# Line_follwer.net
KiCad netlist of a schematic drawn in EAGLE
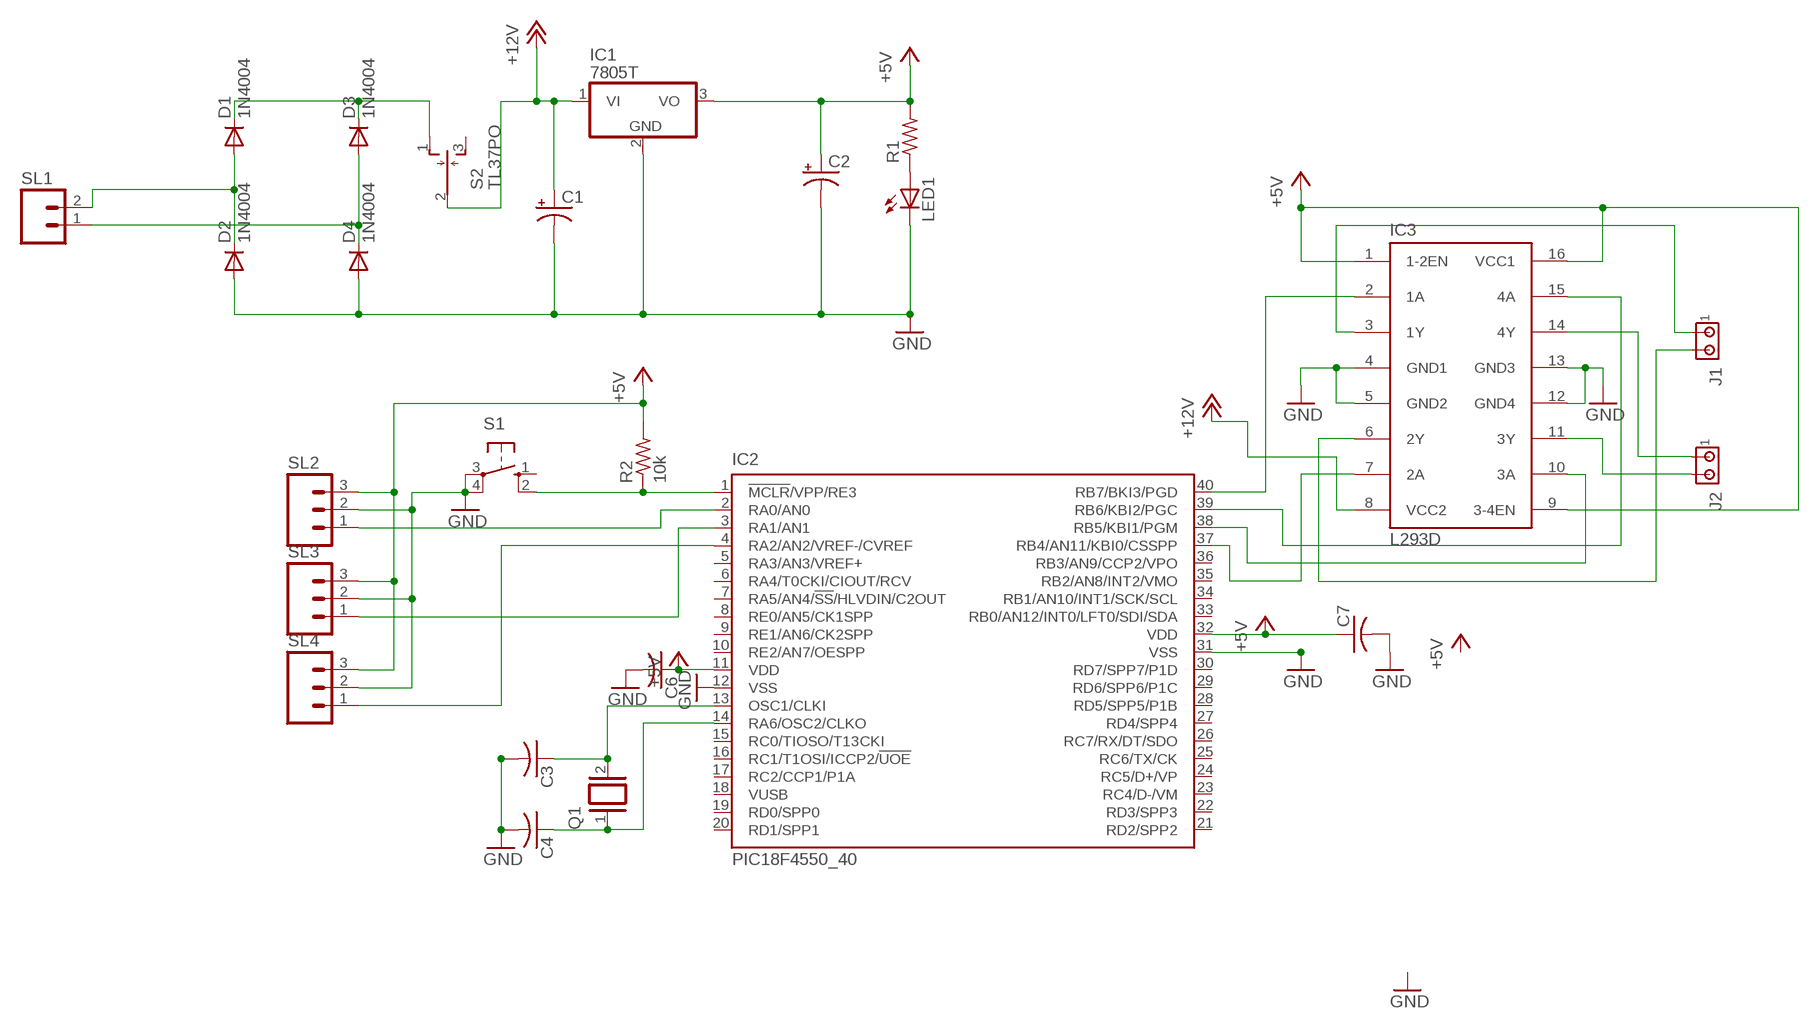
[diagram p0: schematic, sheet 1]

(export (version "E")
  (design (tool "Eeschema 10.0.6"))
  (components
    (comp (ref "C1")
      (value "CPOL-USE3.5-8")
      (footprint "eagle-import:E3,5-8")
      (libsource (lib "eagle-import") (part "CPOL-USE3.5-8"))
    )
    (comp (ref "C2")
      (value "CPOL-USE3.5-8")
      (footprint "eagle-import:E3,5-8")
      (libsource (lib "eagle-import") (part "CPOL-USE3.5-8"))
    )
    (comp (ref "C3")
      (value "C-US025-024X044")
      (footprint "eagle-import:C025-024X044")
      (libsource (lib "eagle-import") (part "C-US025-024X044"))
    )
    (comp (ref "C4")
      (value "C-US025-024X044")
      (footprint "eagle-import:C025-024X044")
      (libsource (lib "eagle-import") (part "C-US025-024X044"))
    )
    (comp (ref "C6")
      (value "C-US025-024X044")
      (footprint "eagle-import:C025-024X044")
      (libsource (lib "eagle-import") (part "C-US025-024X044"))
    )
    (comp (ref "C7")
      (value "C-US025-024X044")
      (footprint "eagle-import:C025-024X044")
      (libsource (lib "eagle-import") (part "C-US025-024X044"))
    )
    (comp (ref "D1")
      (value "1N4004")
      (footprint "eagle-import:DO41-10")
      (libsource (lib "eagle-import") (part "1N4004"))
    )
    (comp (ref "D2")
      (value "1N4004")
      (footprint "eagle-import:DO41-10")
      (libsource (lib "eagle-import") (part "1N4004"))
    )
    (comp (ref "D3")
      (value "1N4004")
      (footprint "eagle-import:DO41-10")
      (libsource (lib "eagle-import") (part "1N4004"))
    )
    (comp (ref "D4")
      (value "1N4004")
      (footprint "eagle-import:DO41-10")
      (libsource (lib "eagle-import") (part "1N4004"))
    )
    (comp (ref "IC1")
      (value "7805T")
      (footprint "eagle-import:TO220H")
      (libsource (lib "eagle-import") (part "78T05"))
    )
    (comp (ref "IC2")
      (value "PIC18F4550_40")
      (footprint "eagle-import:DIL40")
      (fields (field (name "MF") "MICROCHIP") (field (name "MPN") "PIC18F4550-I/P"))
      (libsource (lib "eagle-import") (part "PIC18F4_40550"))
    )
    (comp (ref "IC3")
      (value "L293D")
      (footprint "eagle-import:DIL16")
      (libsource (lib "eagle-import") (part "L293D"))
    )
    (comp (ref "J1")
      (value "MTA02-100")
      (footprint "eagle-import:10X02MTA")
      (libsource (lib "eagle-import") (part "MTA02-100"))
    )
    (comp (ref "J2")
      (value "MTA02-100")
      (footprint "eagle-import:10X02MTA")
      (libsource (lib "eagle-import") (part "MTA02-100"))
    )
    (comp (ref "LED1")
      (value "LED5MM")
      (footprint "eagle-import:LED5MM")
      (libsource (lib "eagle-import") (part "LED5MM"))
    )
    (comp (ref "Q1")
      (value "XTAL/S")
      (footprint "eagle-import:QS")
      (libsource (lib "eagle-import") (part "XTAL/S"))
    )
    (comp (ref "R1")
      (value "R-US_0207/10")
      (footprint "eagle-import:0207_10")
      (libsource (lib "eagle-import") (part "R-US_0207/10"))
    )
    (comp (ref "R2")
      (value "10k")
      (footprint "eagle-import:0207_10")
      (libsource (lib "eagle-import") (part "R-US_0207/10"))
    )
    (comp (ref "S1")
      (value "10-XX")
      (footprint "eagle-import:B3F-10XX")
      (fields (field (name "MPN") "B3F-1000"))
      (libsource (lib "eagle-import") (part "10-XX"))
    )
    (comp (ref "S2")
      (value "TL37PO")
      (footprint "eagle-import:TL3XPO")
      (libsource (lib "eagle-import") (part "TL37PO"))
    )
    (comp (ref "SL1")
      (value "MA02")
      (footprint "eagle-import:02PA")
      (libsource (lib "eagle-import") (part "MA02"))
    )
    (comp (ref "SL2")
      (value "MA03")
      (footprint "eagle-import:03P")
      (libsource (lib "eagle-import") (part "MA03"))
    )
    (comp (ref "SL3")
      (value "MA03")
      (footprint "eagle-import:03P")
      (libsource (lib "eagle-import") (part "MA03"))
    )
    (comp (ref "SL4")
      (value "MA03")
      (footprint "eagle-import:03P")
      (libsource (lib "eagle-import") (part "MA03"))
    )
  )
  (nets
    (net (code "1") (name "+5V") (class "Default")
      (node (ref "C2") (pin "+") (pinfunction "+_+") (pintype "passive"))
      (node (ref "C6") (pin "1") (pinfunction "1_1") (pintype "passive"))
      (node (ref "C7") (pin "1") (pinfunction "1_1") (pintype "passive"))
      (node (ref "IC1") (pin "3") (pinfunction "VO_3") (pintype "passive"))
      (node (ref "IC2") (pin "11") (pinfunction "VDD_11") (pintype "power_in"))
      (node (ref "IC2") (pin "32") (pinfunction "VDD_32") (pintype "power_in"))
      (node (ref "IC3") (pin "1") (pinfunction "1-2EN_1") (pintype "input"))
      (node (ref "IC3") (pin "16") (pinfunction "VCC1_16") (pintype "power_in"))
      (node (ref "IC3") (pin "9") (pinfunction "3-4EN_9") (pintype "input"))
      (node (ref "R1") (pin "2") (pinfunction "2_2") (pintype "passive"))
      (node (ref "R2") (pin "2") (pinfunction "2_2") (pintype "passive"))
      (node (ref "SL2") (pin "3") (pinfunction "3_3") (pintype "passive"))
      (node (ref "SL3") (pin "3") (pinfunction "3_3") (pintype "passive"))
      (node (ref "SL4") (pin "3") (pinfunction "3_3") (pintype "passive"))
    )
    (net (code "2") (name "+12V") (class "Default")
      (node (ref "C1") (pin "+") (pinfunction "+_+") (pintype "passive"))
      (node (ref "IC1") (pin "1") (pinfunction "VI_1") (pintype "input"))
      (node (ref "IC3") (pin "8") (pinfunction "VCC2_8") (pintype "power_in"))
      (node (ref "S2") (pin "2") (pinfunction "P_2") (pintype "passive"))
    )
    (net (code "3") (name "GND") (class "Default")
      (node (ref "C1") (pin "-") (pinfunction "-_-") (pintype "passive"))
      (node (ref "C2") (pin "-") (pinfunction "-_-") (pintype "passive"))
      (node (ref "C3") (pin "2") (pinfunction "2_2") (pintype "passive"))
      (node (ref "C4") (pin "2") (pinfunction "2_2") (pintype "passive"))
      (node (ref "C6") (pin "2") (pinfunction "2_2") (pintype "passive"))
      (node (ref "C7") (pin "2") (pinfunction "2_2") (pintype "passive"))
      (node (ref "D2") (pin "A") (pinfunction "A_A") (pintype "passive"))
      (node (ref "D4") (pin "A") (pinfunction "A_A") (pintype "passive"))
      (node (ref "IC1") (pin "2") (pinfunction "GND_2") (pintype "passive"))
      (node (ref "IC2") (pin "12") (pinfunction "VSS_12") (pintype "power_in"))
      (node (ref "IC2") (pin "31") (pinfunction "VSS_31") (pintype "power_in"))
      (node (ref "IC3") (pin "12") (pinfunction "GND4_12") (pintype "power_in"))
      (node (ref "IC3") (pin "13") (pinfunction "GND3_13") (pintype "power_in"))
      (node (ref "IC3") (pin "4") (pinfunction "GND1_4") (pintype "power_in"))
      (node (ref "IC3") (pin "5") (pinfunction "GND2_5") (pintype "power_in"))
      (node (ref "LED1") (pin "K") (pinfunction "C_K") (pintype "passive"))
      (node (ref "S1") (pin "3") (pinfunction "P_3") (pintype "passive"))
      (node (ref "S1") (pin "4") (pinfunction "P1_4") (pintype "passive"))
      (node (ref "SL2") (pin "2") (pinfunction "2_2") (pintype "passive"))
      (node (ref "SL3") (pin "2") (pinfunction "2_2") (pintype "passive"))
      (node (ref "SL4") (pin "2") (pinfunction "2_2") (pintype "passive"))
    )
    (net (code "4") (name "Net-(D1-PadA)") (class "Default")
      (node (ref "D1") (pin "A") (pinfunction "A_A") (pintype "passive"))
      (node (ref "D2") (pin "C") (pinfunction "C_C") (pintype "passive"))
      (node (ref "SL1") (pin "2") (pinfunction "2_2") (pintype "passive"))
    )
    (net (code "5") (name "Net-(D3-PadA)") (class "Default")
      (node (ref "D3") (pin "A") (pinfunction "A_A") (pintype "passive"))
      (node (ref "D4") (pin "C") (pinfunction "C_C") (pintype "passive"))
      (node (ref "SL1") (pin "1") (pinfunction "1_1") (pintype "passive"))
    )
    (net (code "6") (name "Net-(IC2-OSC1{slash}CLKI)") (class "Default")
      (node (ref "C3") (pin "1") (pinfunction "1_1") (pintype "passive"))
      (node (ref "IC2") (pin "13") (pinfunction "OSC1/CLKI_13") (pintype "input"))
      (node (ref "Q1") (pin "2") (pinfunction "2_2") (pintype "passive"))
    )
    (net (code "7") (name "Net-(IC2-RA0{slash}AN0)") (class "Default")
      (node (ref "IC2") (pin "2") (pinfunction "RA0/AN0_2") (pintype "bidirectional"))
      (node (ref "SL2") (pin "1") (pinfunction "1_1") (pintype "passive"))
    )
    (net (code "8") (name "Net-(IC2-RA1{slash}AN1)") (class "Default")
      (node (ref "IC2") (pin "3") (pinfunction "RA1/AN1_3") (pintype "bidirectional"))
      (node (ref "SL3") (pin "1") (pinfunction "1_1") (pintype "passive"))
    )
    (net (code "9") (name "Net-(IC2-RA2{slash}AN2{slash}VREF-{slash}CVREF)") (class "Default")
      (node (ref "IC2") (pin "4") (pinfunction "RA2/AN2/VREF-/CVREF_4") (pintype "bidirectional"))
      (node (ref "SL4") (pin "1") (pinfunction "1_1") (pintype "passive"))
    )
    (net (code "10") (name "Net-(IC2-RA6{slash}OSC2{slash}CLKO)") (class "Default")
      (node (ref "C4") (pin "1") (pinfunction "1_1") (pintype "passive"))
      (node (ref "IC2") (pin "14") (pinfunction "RA6/OSC2/CLKO_14") (pintype "output"))
      (node (ref "Q1") (pin "1") (pinfunction "1_1") (pintype "passive"))
    )
    (net (code "11") (name "Net-(IC2-RB4{slash}AN11{slash}KBI0{slash}CSSPP)") (class "Default")
      (node (ref "IC2") (pin "37") (pinfunction "RB4/AN11/KBI0/CSSPP_37") (pintype "bidirectional"))
      (node (ref "IC3") (pin "7") (pinfunction "2A_7") (pintype "input"))
    )
    (net (code "12") (name "Net-(IC2-RB5{slash}KBI1{slash}PGM)") (class "Default")
      (node (ref "IC2") (pin "38") (pinfunction "RB5/KBI1/PGM_38") (pintype "bidirectional"))
      (node (ref "IC3") (pin "10") (pinfunction "3A_10") (pintype "input"))
    )
    (net (code "13") (name "Net-(IC2-RB6{slash}KBI2{slash}PGC)") (class "Default")
      (node (ref "IC2") (pin "39") (pinfunction "RB6/KBI2/PGC_39") (pintype "bidirectional"))
      (node (ref "IC3") (pin "15") (pinfunction "4A_15") (pintype "input"))
    )
    (net (code "14") (name "Net-(IC2-RB7{slash}BKI3{slash}PGD)") (class "Default")
      (node (ref "IC2") (pin "40") (pinfunction "RB7/BKI3/PGD_40") (pintype "bidirectional"))
      (node (ref "IC3") (pin "2") (pinfunction "1A_2") (pintype "input"))
    )
    (net (code "15") (name "Net-(IC2-~{MCLR}{slash}VPP{slash}RE3)") (class "Default")
      (node (ref "IC2") (pin "1") (pinfunction "~{MCLR}/VPP/RE3_1") (pintype "input"))
      (node (ref "R2") (pin "1") (pinfunction "1_1") (pintype "passive"))
      (node (ref "S1") (pin "2") (pinfunction "S1_2") (pintype "passive"))
    )
    (net (code "16") (name "Net-(IC3-1Y)") (class "Default")
      (node (ref "IC3") (pin "3") (pinfunction "1Y_3") (pintype "output"))
      (node (ref "J1") (pin "1") (pinfunction "1_1") (pintype "passive"))
    )
    (net (code "17") (name "Net-(IC3-2Y)") (class "Default")
      (node (ref "IC3") (pin "6") (pinfunction "2Y_6") (pintype "output"))
      (node (ref "J1") (pin "2") (pinfunction "2_2") (pintype "passive"))
    )
    (net (code "18") (name "Net-(IC3-3Y)") (class "Default")
      (node (ref "IC3") (pin "11") (pinfunction "3Y_11") (pintype "output"))
      (node (ref "J2") (pin "2") (pinfunction "2_2") (pintype "passive"))
    )
    (net (code "19") (name "Net-(IC3-4Y)") (class "Default")
      (node (ref "IC3") (pin "14") (pinfunction "4Y_14") (pintype "output"))
      (node (ref "J2") (pin "1") (pinfunction "1_1") (pintype "passive"))
    )
    (net (code "20") (name "Net-(LED1-PadA)") (class "Default")
      (node (ref "LED1") (pin "A") (pinfunction "A_A") (pintype "passive"))
      (node (ref "R1") (pin "1") (pinfunction "1_1") (pintype "passive"))
    )
    (net (code "21") (name "Net-(S2-O)") (class "Default")
      (node (ref "D1") (pin "C") (pinfunction "C_C") (pintype "passive"))
      (node (ref "D3") (pin "C") (pinfunction "C_C") (pintype "passive"))
      (node (ref "S2") (pin "1") (pinfunction "O_1") (pintype "passive"))
    )
    (net (code "22") (name "unconnected-(IC2-RA3{slash}AN3{slash}VREF+-Pad5)") (class "Default")
      (node (ref "IC2") (pin "5") (pinfunction "RA3/AN3/VREF+_5") (pintype "bidirectional"))
    )
    (net (code "23") (name "unconnected-(IC2-RA4{slash}T0CKI{slash}CIOUT{slash}RCV-Pad6)") (class "Default")
      (node (ref "IC2") (pin "6") (pinfunction "RA4/T0CKI/CIOUT/RCV_6") (pintype "bidirectional"))
    )
    (net (code "24") (name "unconnected-(IC2-RA5{slash}AN4{slash}~{SS}{slash}HLVDIN{slash}C2OUT-Pad7)") (class "Default")
      (node (ref "IC2") (pin "7") (pinfunction "RA5/AN4/~{SS}/HLVDIN/C2OUT_7") (pintype "bidirectional"))
    )
    (net (code "25") (name "unconnected-(IC2-RB0{slash}AN12{slash}INT0{slash}LFT0{slash}SDI{slash}SDA-Pad33)") (class "Default")
      (node (ref "IC2") (pin "33") (pinfunction "RB0/AN12/INT0/LFT0/SDI/SDA_33") (pintype "bidirectional"))
    )
    (net (code "26") (name "unconnected-(IC2-RB1{slash}AN10{slash}INT1{slash}SCK{slash}SCL-Pad34)") (class "Default")
      (node (ref "IC2") (pin "34") (pinfunction "RB1/AN10/INT1/SCK/SCL_34") (pintype "bidirectional"))
    )
    (net (code "27") (name "unconnected-(IC2-RB2{slash}AN8{slash}INT2{slash}VMO-Pad35)") (class "Default")
      (node (ref "IC2") (pin "35") (pinfunction "RB2/AN8/INT2/VMO_35") (pintype "bidirectional"))
    )
    (net (code "28") (name "unconnected-(IC2-RB3{slash}AN9{slash}CCP2{slash}VPO-Pad36)") (class "Default")
      (node (ref "IC2") (pin "36") (pinfunction "RB3/AN9/CCP2/VPO_36") (pintype "bidirectional"))
    )
    (net (code "29") (name "unconnected-(IC2-RC0{slash}TIOSO{slash}T13CKI-Pad15)") (class "Default")
      (node (ref "IC2") (pin "15") (pinfunction "RC0/TIOSO/T13CKI_15") (pintype "bidirectional"))
    )
    (net (code "30") (name "unconnected-(IC2-RC1{slash}T1OSI{slash}ICCP2{slash}~{UOE}-Pad16)") (class "Default")
      (node (ref "IC2") (pin "16") (pinfunction "RC1/T1OSI/ICCP2/~{UOE}_16") (pintype "bidirectional"))
    )
    (net (code "31") (name "unconnected-(IC2-RC2{slash}CCP1{slash}P1A-Pad17)") (class "Default")
      (node (ref "IC2") (pin "17") (pinfunction "RC2/CCP1/P1A_17") (pintype "bidirectional"))
    )
    (net (code "32") (name "unconnected-(IC2-RC4{slash}D-{slash}VM-Pad23)") (class "Default")
      (node (ref "IC2") (pin "23") (pinfunction "RC4/D-/VM_23") (pintype "bidirectional"))
    )
    (net (code "33") (name "unconnected-(IC2-RC5{slash}D+{slash}VP-Pad24)") (class "Default")
      (node (ref "IC2") (pin "24") (pinfunction "RC5/D+/VP_24") (pintype "bidirectional"))
    )
    (net (code "34") (name "unconnected-(IC2-RC6{slash}TX{slash}CK-Pad25)") (class "Default")
      (node (ref "IC2") (pin "25") (pinfunction "RC6/TX/CK_25") (pintype "bidirectional"))
    )
    (net (code "35") (name "unconnected-(IC2-RC7{slash}RX{slash}DT{slash}SDO-Pad26)") (class "Default")
      (node (ref "IC2") (pin "26") (pinfunction "RC7/RX/DT/SDO_26") (pintype "bidirectional"))
    )
    (net (code "36") (name "unconnected-(IC2-RD0{slash}SPP0-Pad19)") (class "Default")
      (node (ref "IC2") (pin "19") (pinfunction "RD0/SPP0_19") (pintype "bidirectional"))
    )
    (net (code "37") (name "unconnected-(IC2-RD1{slash}SPP1-Pad20)") (class "Default")
      (node (ref "IC2") (pin "20") (pinfunction "RD1/SPP1_20") (pintype "bidirectional"))
    )
    (net (code "38") (name "unconnected-(IC2-RD2{slash}SPP2-Pad21)") (class "Default")
      (node (ref "IC2") (pin "21") (pinfunction "RD2/SPP2_21") (pintype "bidirectional"))
    )
    (net (code "39") (name "unconnected-(IC2-RD3{slash}SPP3-Pad22)") (class "Default")
      (node (ref "IC2") (pin "22") (pinfunction "RD3/SPP3_22") (pintype "bidirectional"))
    )
    (net (code "40") (name "unconnected-(IC2-RD4{slash}SPP4-Pad27)") (class "Default")
      (node (ref "IC2") (pin "27") (pinfunction "RD4/SPP4_27") (pintype "bidirectional"))
    )
    (net (code "41") (name "unconnected-(IC2-RD5{slash}SPP5{slash}P1B-Pad28)") (class "Default")
      (node (ref "IC2") (pin "28") (pinfunction "RD5/SPP5/P1B_28") (pintype "bidirectional"))
    )
    (net (code "42") (name "unconnected-(IC2-RD6{slash}SPP6{slash}P1C-Pad29)") (class "Default")
      (node (ref "IC2") (pin "29") (pinfunction "RD6/SPP6/P1C_29") (pintype "bidirectional"))
    )
    (net (code "43") (name "unconnected-(IC2-RD7{slash}SPP7{slash}P1D-Pad30)") (class "Default")
      (node (ref "IC2") (pin "30") (pinfunction "RD7/SPP7/P1D_30") (pintype "bidirectional"))
    )
    (net (code "44") (name "unconnected-(IC2-RE0{slash}AN5{slash}CK1SPP-Pad8)") (class "Default")
      (node (ref "IC2") (pin "8") (pinfunction "RE0/AN5/CK1SPP_8") (pintype "bidirectional"))
    )
    (net (code "45") (name "unconnected-(IC2-RE1{slash}AN6{slash}CK2SPP-Pad9)") (class "Default")
      (node (ref "IC2") (pin "9") (pinfunction "RE1/AN6/CK2SPP_9") (pintype "bidirectional"))
    )
    (net (code "46") (name "unconnected-(IC2-RE2{slash}AN7{slash}OESPP-Pad10)") (class "Default")
      (node (ref "IC2") (pin "10") (pinfunction "RE2/AN7/OESPP_10") (pintype "bidirectional"))
    )
    (net (code "47") (name "unconnected-(IC2-VUSB-Pad18)") (class "Default")
      (node (ref "IC2") (pin "18") (pinfunction "VUSB_18") (pintype "bidirectional"))
    )
    (net (code "48") (name "unconnected-(S1-S-Pad1)") (class "Default")
      (node (ref "S1") (pin "1") (pinfunction "S_1") (pintype "passive"))
    )
    (net (code "49") (name "unconnected-(S2-S-Pad3)") (class "Default")
      (node (ref "S2") (pin "3") (pinfunction "S_3") (pintype "passive"))
    )
  )
)
